# AFE.net
KiCad netlist of a schematic drawn in EAGLE
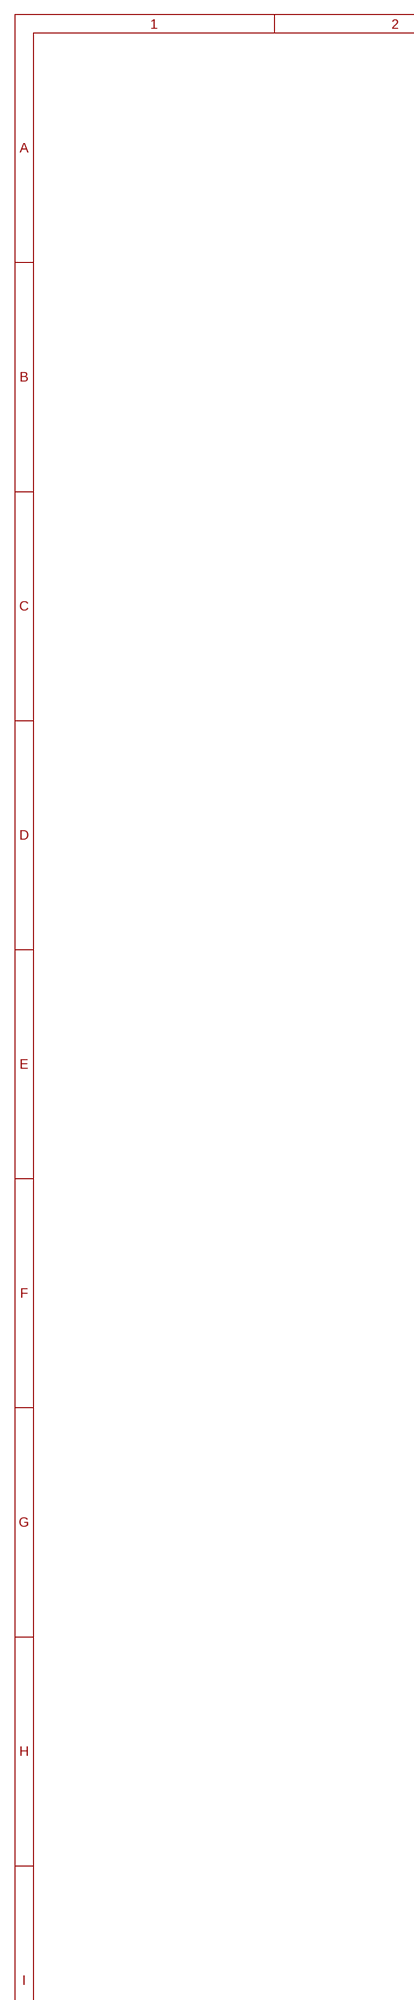
[diagram p0: schematic, sheet 1, part 1 of 2]
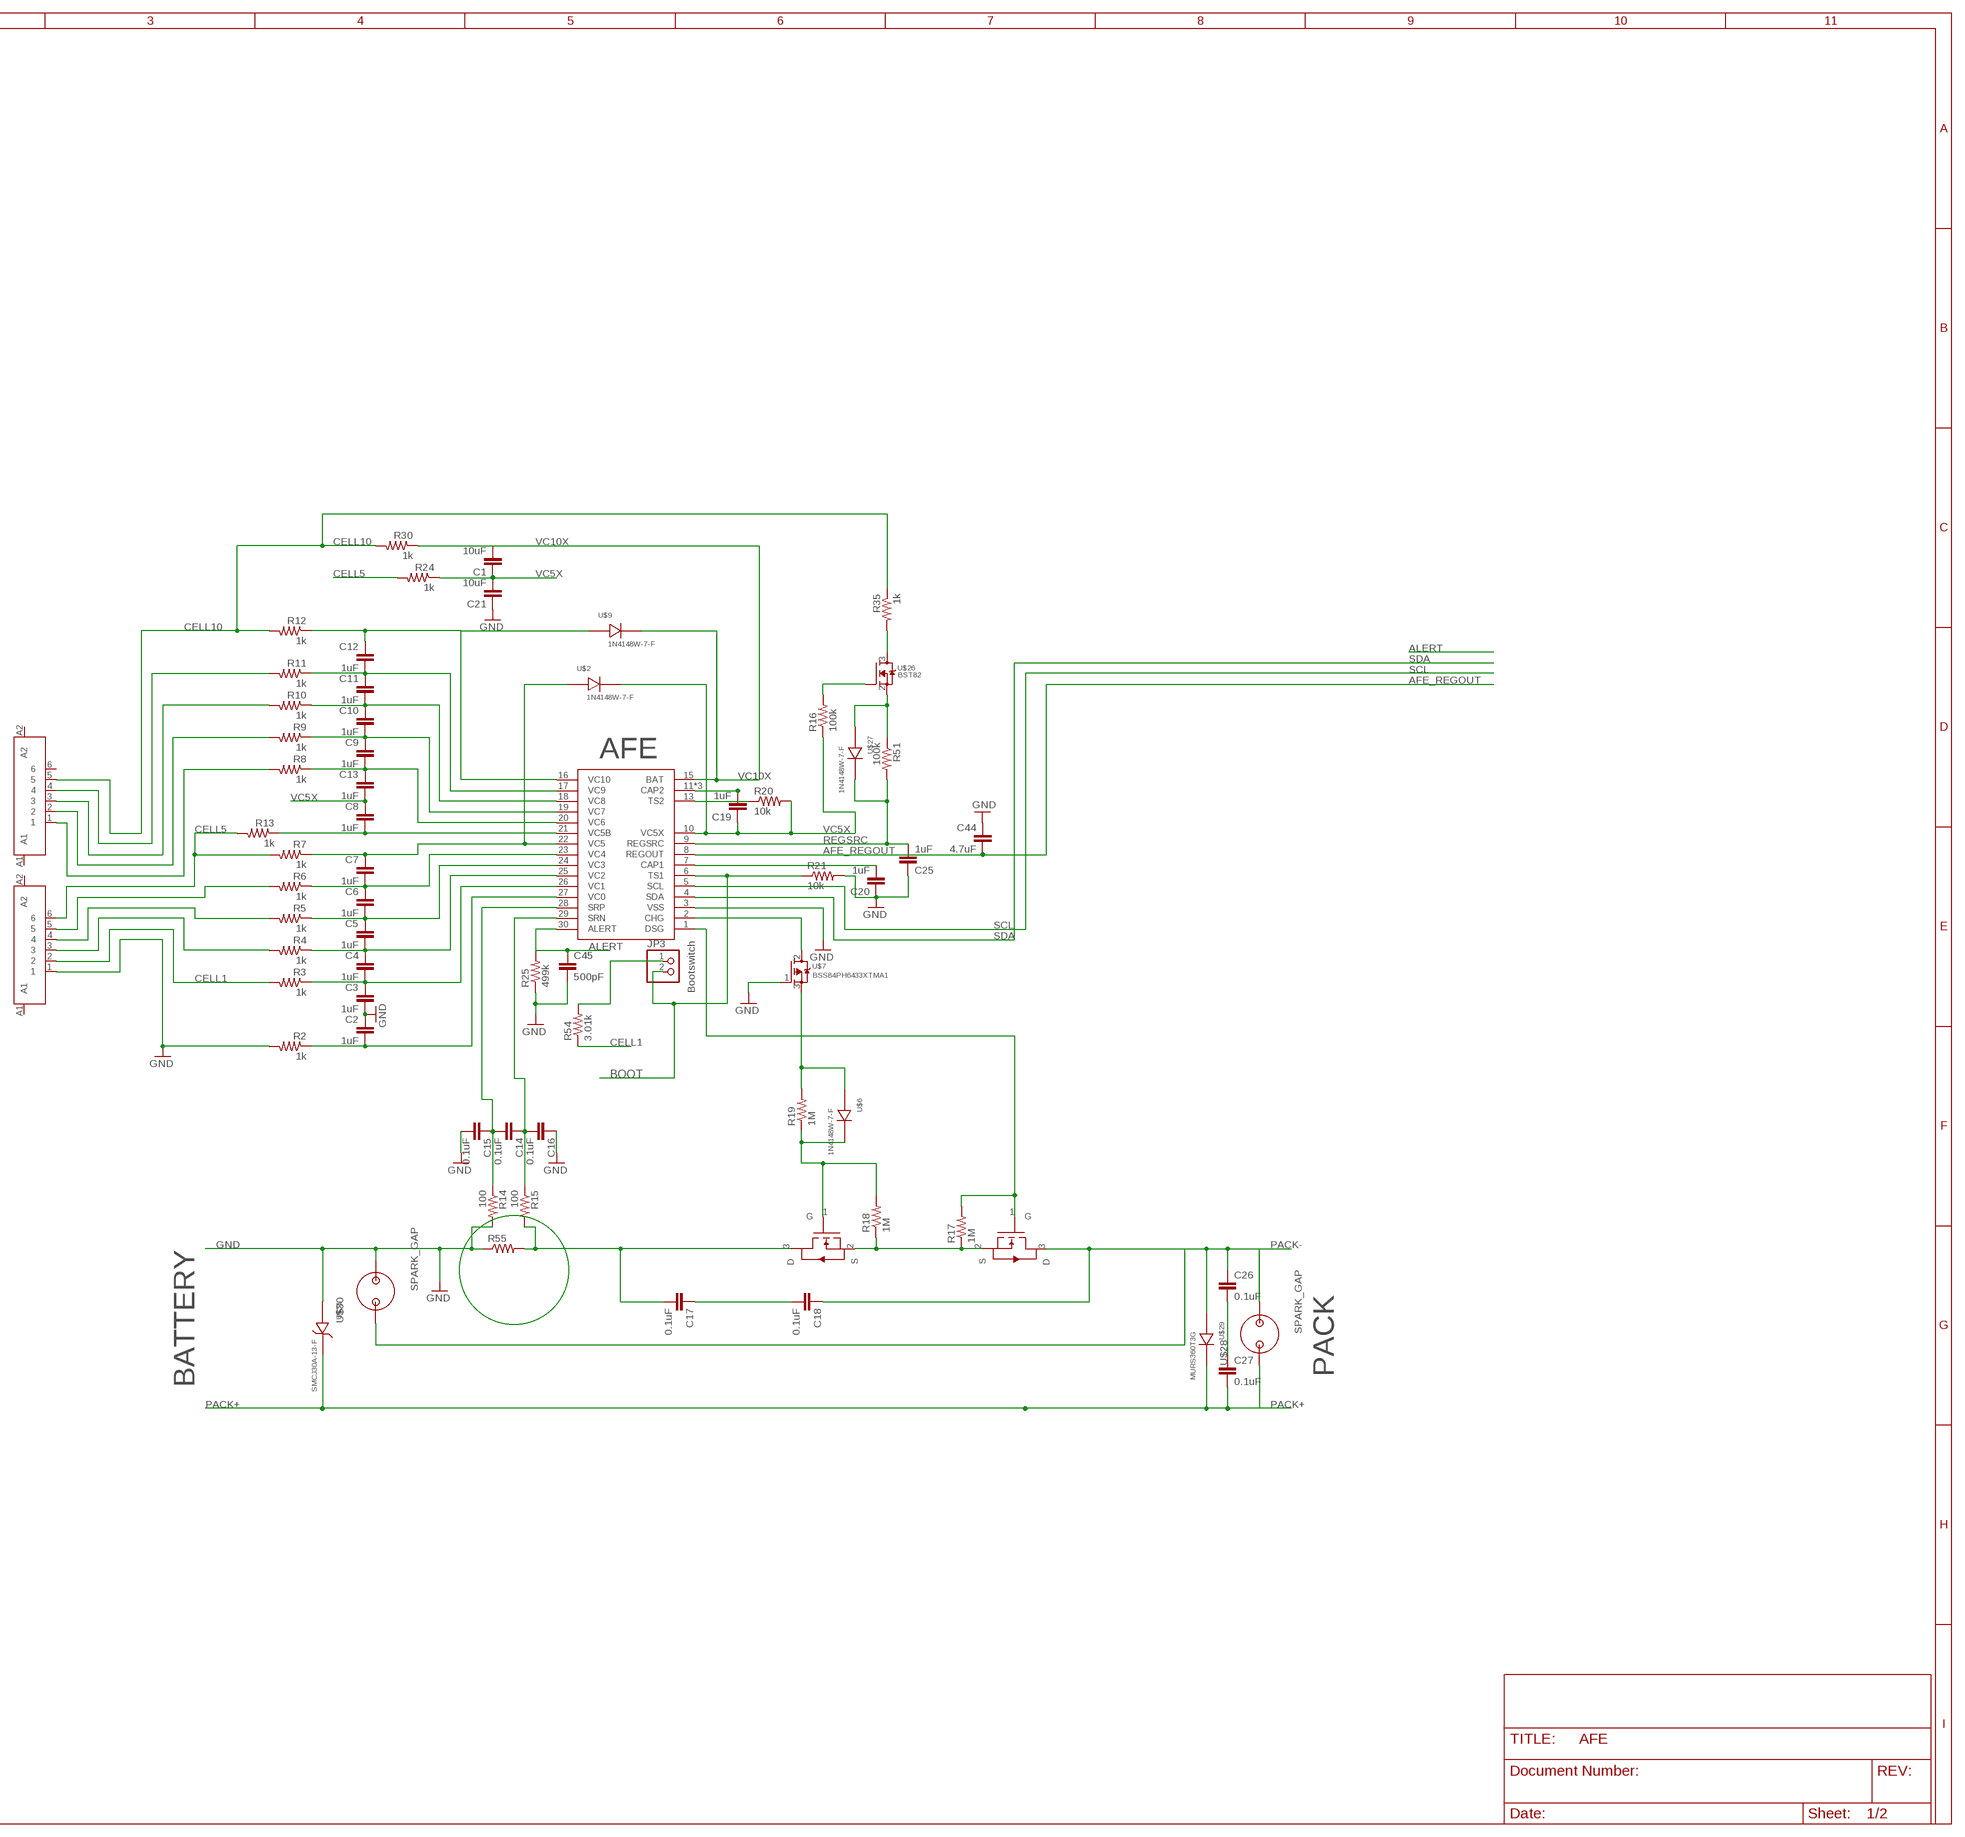
[diagram p1: schematic, sheet 1, part 2 of 2]
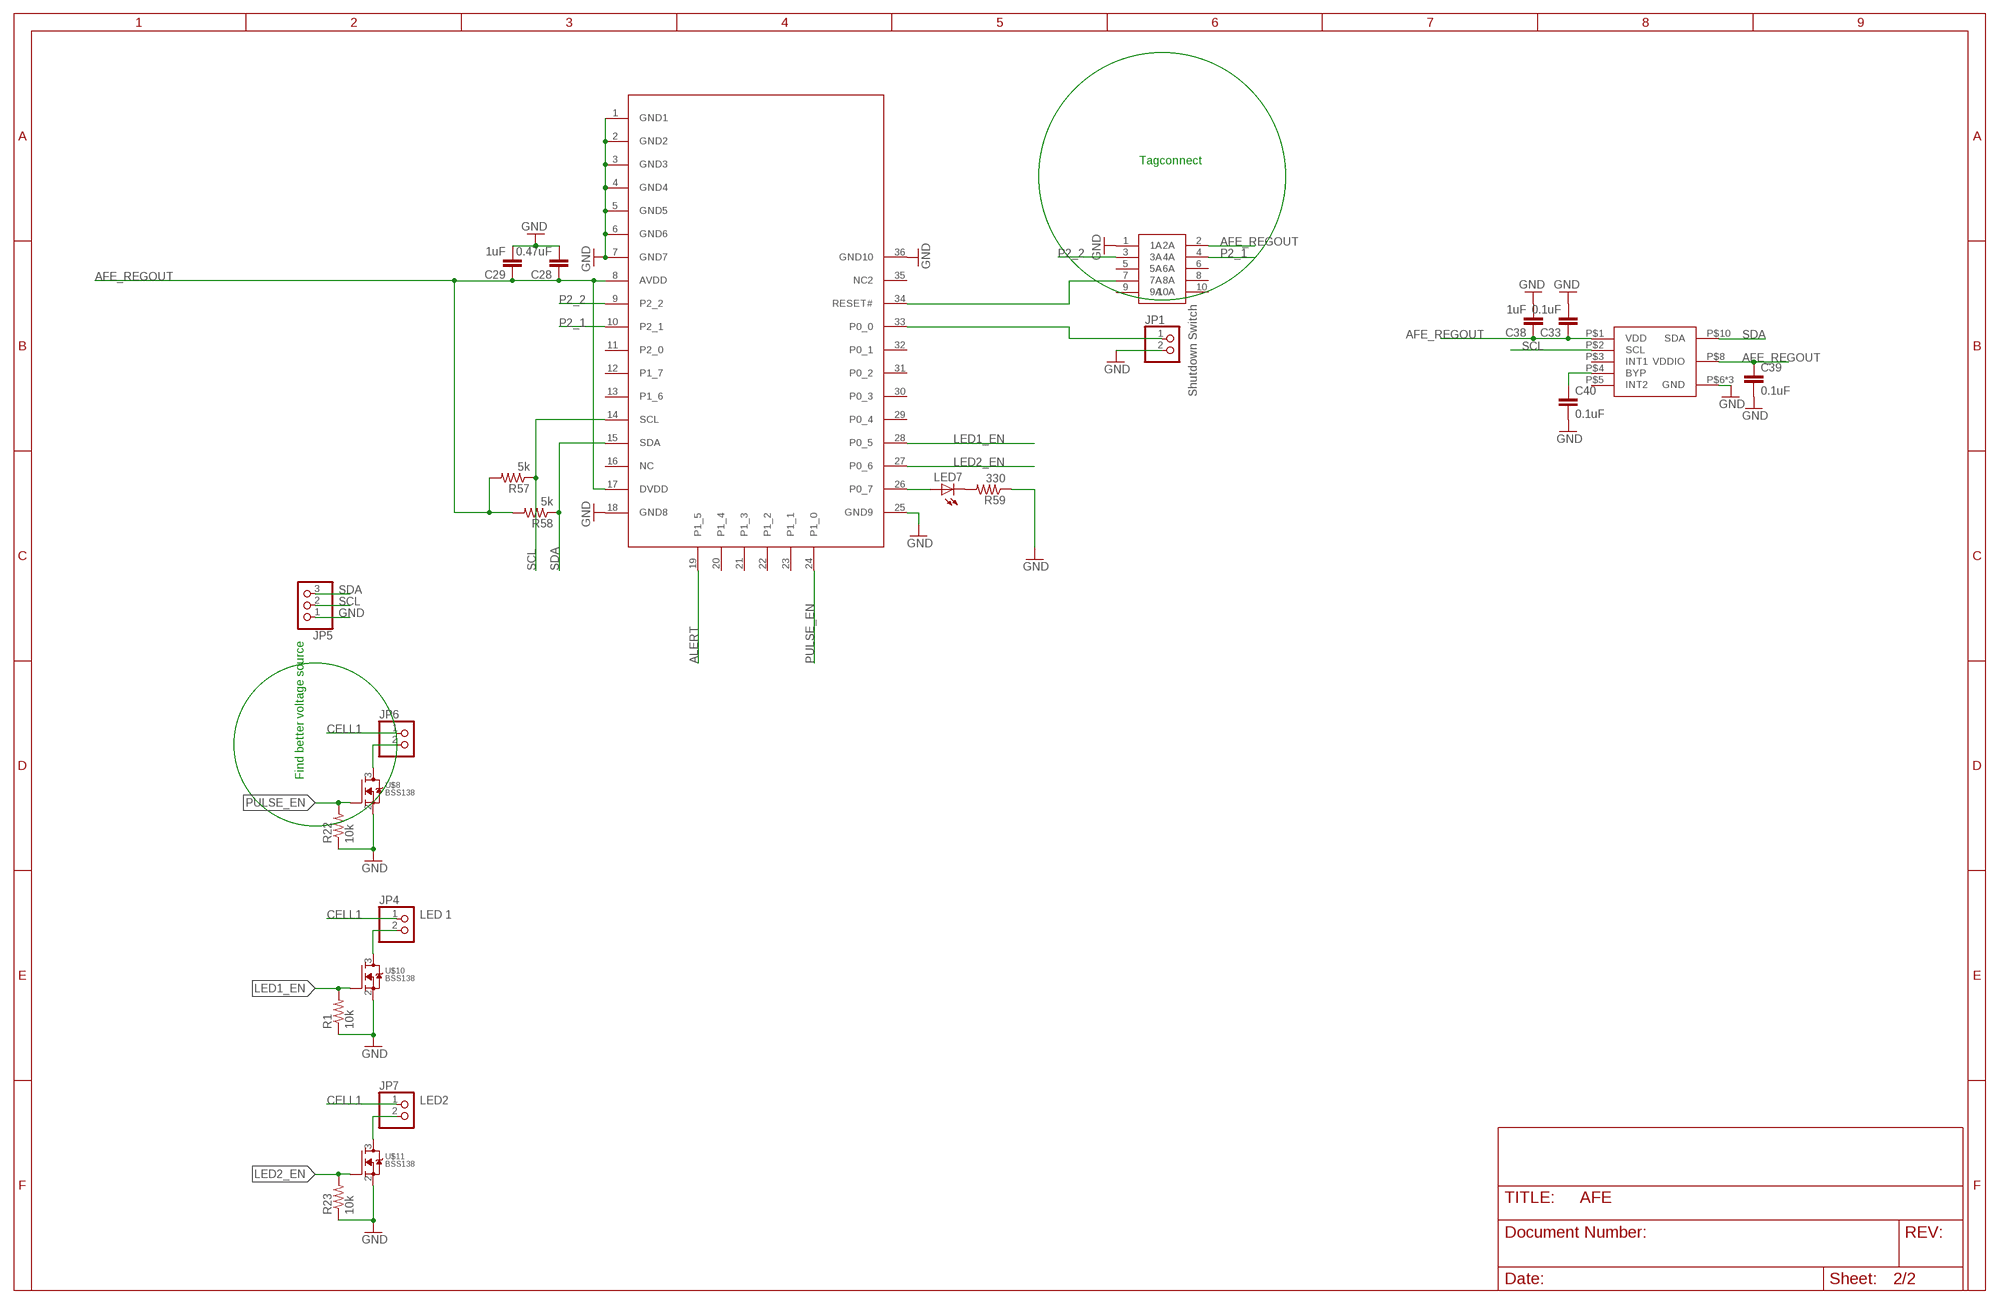
[diagram p2: schematic, sheet 2]

(export (version "E")
  (design (tool "Eeschema 10.0.6"))
  (components
    (comp (ref "C1")
      (value "10uF")
      (footprint "eagle-import:C1210")
      (libsource (lib "eagle-import") (part "C-EUC1210"))
    )
    (comp (ref "C2")
      (value "1uF")
      (footprint "eagle-import:C0805")
      (libsource (lib "eagle-import") (part "C-EUC0805"))
    )
    (comp (ref "C3")
      (value "1uF")
      (footprint "eagle-import:C0805")
      (libsource (lib "eagle-import") (part "C-EUC0805"))
    )
    (comp (ref "C4")
      (value "1uF")
      (footprint "eagle-import:C0805")
      (libsource (lib "eagle-import") (part "C-EUC0805"))
    )
    (comp (ref "C5")
      (value "1uF")
      (footprint "eagle-import:C0805")
      (libsource (lib "eagle-import") (part "C-EUC0805"))
    )
    (comp (ref "C6")
      (value "1uF")
      (footprint "eagle-import:C0805")
      (libsource (lib "eagle-import") (part "C-EUC0805"))
    )
    (comp (ref "C7")
      (value "1uF")
      (footprint "eagle-import:C0805")
      (libsource (lib "eagle-import") (part "C-EUC0805"))
    )
    (comp (ref "C8")
      (value "1uF")
      (footprint "eagle-import:C0805")
      (libsource (lib "eagle-import") (part "C-EUC0805"))
    )
    (comp (ref "C9")
      (value "1uF")
      (footprint "eagle-import:C0805")
      (libsource (lib "eagle-import") (part "C-EUC0805"))
    )
    (comp (ref "C10")
      (value "1uF")
      (footprint "eagle-import:C0805")
      (libsource (lib "eagle-import") (part "C-EUC0805"))
    )
    (comp (ref "C11")
      (value "1uF")
      (footprint "eagle-import:C0805")
      (libsource (lib "eagle-import") (part "C-EUC0805"))
    )
    (comp (ref "C12")
      (value "1uF")
      (footprint "eagle-import:C0805")
      (libsource (lib "eagle-import") (part "C-EUC0805"))
    )
    (comp (ref "C13")
      (value "1uF")
      (footprint "eagle-import:C0805")
      (libsource (lib "eagle-import") (part "C-EUC0805"))
    )
    (comp (ref "C14")
      (value "0.1uF")
      (footprint "eagle-import:C0805")
      (libsource (lib "eagle-import") (part "C-EUC0805"))
    )
    (comp (ref "C15")
      (value "0.1uF")
      (footprint "eagle-import:C0805")
      (libsource (lib "eagle-import") (part "C-EUC0805"))
    )
    (comp (ref "C16")
      (value "0.1uF")
      (footprint "eagle-import:C0805")
      (libsource (lib "eagle-import") (part "C-EUC0805"))
    )
    (comp (ref "C17")
      (value "0.1uF")
      (footprint "eagle-import:C0805")
      (libsource (lib "eagle-import") (part "C-EUC0805"))
    )
    (comp (ref "C18")
      (value "0.1uF")
      (footprint "eagle-import:C0805")
      (libsource (lib "eagle-import") (part "C-EUC0805"))
    )
    (comp (ref "C19")
      (value "1uF")
      (footprint "eagle-import:C0805")
      (libsource (lib "eagle-import") (part "C-EUC0805"))
    )
    (comp (ref "C20")
      (value "1uF")
      (footprint "eagle-import:C0805")
      (libsource (lib "eagle-import") (part "C-EUC0805"))
    )
    (comp (ref "C21")
      (value "10uF")
      (footprint "eagle-import:C1210")
      (libsource (lib "eagle-import") (part "C-EUC1210"))
    )
    (comp (ref "C25")
      (value "1uF")
      (footprint "eagle-import:C0805")
      (libsource (lib "eagle-import") (part "C-EUC0805"))
    )
    (comp (ref "C26")
      (value "0.1uF")
      (footprint "eagle-import:C0805")
      (libsource (lib "eagle-import") (part "C-EUC0805"))
    )
    (comp (ref "C27")
      (value "0.1uF")
      (footprint "eagle-import:C0805")
      (libsource (lib "eagle-import") (part "C-EUC0805"))
    )
    (comp (ref "C44")
      (value "4.7uF")
      (footprint "eagle-import:C0805")
      (libsource (lib "eagle-import") (part "C-EUC0805"))
    )
    (comp (ref "C45")
      (value "500pF")
      (footprint "eagle-import:C0603")
      (libsource (lib "eagle-import") (part "C-EUC0603"))
    )
    (comp (ref "JP3")
      (value "PINHD-1X2")
      (footprint "eagle-import:1X02")
      (libsource (lib "eagle-import") (part "PINHD-1X2"))
    )
    (comp (ref "R2")
      (value "1k")
      (footprint "eagle-import:R1206")
      (libsource (lib "eagle-import") (part "R-US_R1206"))
    )
    (comp (ref "R3")
      (value "1k")
      (footprint "eagle-import:R1206")
      (libsource (lib "eagle-import") (part "R-US_R1206"))
    )
    (comp (ref "R4")
      (value "1k")
      (footprint "eagle-import:R1206")
      (libsource (lib "eagle-import") (part "R-US_R1206"))
    )
    (comp (ref "R5")
      (value "1k")
      (footprint "eagle-import:R1206")
      (libsource (lib "eagle-import") (part "R-US_R1206"))
    )
    (comp (ref "R6")
      (value "1k")
      (footprint "eagle-import:R1206")
      (libsource (lib "eagle-import") (part "R-US_R1206"))
    )
    (comp (ref "R7")
      (value "1k")
      (footprint "eagle-import:R1206")
      (libsource (lib "eagle-import") (part "R-US_R1206"))
    )
    (comp (ref "R8")
      (value "1k")
      (footprint "eagle-import:R1206")
      (libsource (lib "eagle-import") (part "R-US_R1206"))
    )
    (comp (ref "R9")
      (value "1k")
      (footprint "eagle-import:R1206")
      (libsource (lib "eagle-import") (part "R-US_R1206"))
    )
    (comp (ref "R10")
      (value "1k")
      (footprint "eagle-import:R1206")
      (libsource (lib "eagle-import") (part "R-US_R1206"))
    )
    (comp (ref "R11")
      (value "1k")
      (footprint "eagle-import:R1206")
      (libsource (lib "eagle-import") (part "R-US_R1206"))
    )
    (comp (ref "R12")
      (value "1k")
      (footprint "eagle-import:R1206")
      (libsource (lib "eagle-import") (part "R-US_R1206"))
    )
    (comp (ref "R13")
      (value "1k")
      (footprint "eagle-import:R1206")
      (libsource (lib "eagle-import") (part "R-US_R1206"))
    )
    (comp (ref "R14")
      (value "100")
      (footprint "eagle-import:R0805")
      (libsource (lib "eagle-import") (part "R-US_R0805"))
    )
    (comp (ref "R15")
      (value "100")
      (footprint "eagle-import:R0805")
      (libsource (lib "eagle-import") (part "R-US_R0805"))
    )
    (comp (ref "R16")
      (value "100k")
      (footprint "eagle-import:R0805")
      (libsource (lib "eagle-import") (part "R-US_R0805"))
    )
    (comp (ref "R17")
      (value "1M")
      (footprint "eagle-import:R1206")
      (libsource (lib "eagle-import") (part "R-US_R1206"))
    )
    (comp (ref "R18")
      (value "1M")
      (footprint "eagle-import:R1206")
      (libsource (lib "eagle-import") (part "R-US_R1206"))
    )
    (comp (ref "R19")
      (value "1M")
      (footprint "eagle-import:R1206")
      (libsource (lib "eagle-import") (part "R-US_R1206"))
    )
    (comp (ref "R20")
      (value "10k")
      (footprint "eagle-import:R0805")
      (libsource (lib "eagle-import") (part "R-US_R0805"))
    )
    (comp (ref "R21")
      (value "10k")
      (footprint "eagle-import:R0805")
      (libsource (lib "eagle-import") (part "R-US_R0805"))
    )
    (comp (ref "R24")
      (value "1k")
      (footprint "eagle-import:R1206")
      (libsource (lib "eagle-import") (part "R-US_R1206"))
    )
    (comp (ref "R25")
      (value "499k")
      (footprint "eagle-import:R0603")
      (libsource (lib "eagle-import") (part "R-US_R0603"))
    )
    (comp (ref "R30")
      (value "1k")
      (footprint "eagle-import:R1206")
      (libsource (lib "eagle-import") (part "R-US_R1206"))
    )
    (comp (ref "R35")
      (value "1k")
      (footprint "eagle-import:R1206")
      (libsource (lib "eagle-import") (part "R-US_R1206"))
    )
    (comp (ref "R51")
      (value "100k")
      (footprint "eagle-import:R0805")
      (libsource (lib "eagle-import") (part "R-US_R0805"))
    )
    (comp (ref "R54")
      (value "3.01k")
      (footprint "eagle-import:R1206")
      (libsource (lib "eagle-import") (part "R-US_R1206"))
    )
    (comp (ref "R55")
      (value "R-US_R2512")
      (footprint "eagle-import:R2512")
      (libsource (lib "eagle-import") (part "R-US_R2512"))
    )
    (comp (ref "U$1")
      (value "BQ76930")
      (footprint "eagle-import:SOIC-30")
      (libsource (lib "eagle-import") (part "BQ76930"))
    )
    (comp (ref "U$2")
      (value "1N4148W-7-F")
      (footprint "eagle-import:SOD-123")
      (libsource (lib "eagle-import") (part "1N4148W-7-F"))
    )
    (comp (ref "U$4")
      (value "AOB290L")
      (footprint "eagle-import:TO-263")
      (libsource (lib "eagle-import") (part "AOB290L"))
    )
    (comp (ref "U$5")
      (value "AOB290L")
      (footprint "eagle-import:TO-263")
      (libsource (lib "eagle-import") (part "AOB290L"))
    )
    (comp (ref "U$6")
      (value "1N4148W-7-F")
      (footprint "eagle-import:SOD-123")
      (libsource (lib "eagle-import") (part "1N4148W-7-F"))
    )
    (comp (ref "U$7")
      (value "BSS84PH6433XTMA1")
      (footprint "eagle-import:SOT23-3")
      (libsource (lib "eagle-import") (part "BSS84PH6433XTMA1"))
    )
    (comp (ref "U$9")
      (value "1N4148W-7-F")
      (footprint "eagle-import:SOD-123")
      (libsource (lib "eagle-import") (part "1N4148W-7-F"))
    )
    (comp (ref "U$24")
      (value "JST_6PIN")
      (footprint "eagle-import:JST_6PIN")
      (libsource (lib "eagle-import") (part "JST_6PIN"))
    )
    (comp (ref "U$26")
      (value "BST82")
      (footprint "eagle-import:SOT23-3")
      (libsource (lib "eagle-import") (part "BST82"))
    )
    (comp (ref "U$27")
      (value "1N4148W-7-F")
      (footprint "eagle-import:SOD-123")
      (libsource (lib "eagle-import") (part "1N4148W-7-F"))
    )
    (comp (ref "U$28")
      (value "SPARK_GAP")
      (footprint "eagle-import:SPARK_GAP")
      (libsource (lib "eagle-import") (part "SPARK_GAP"))
    )
    (comp (ref "U$29")
      (value "MURS360T3G")
      (footprint "eagle-import:SMC(DO-214AB)")
      (libsource (lib "eagle-import") (part "MURS360T3G"))
    )
    (comp (ref "U$30")
      (value "SPARK_GAP")
      (footprint "eagle-import:SPARK_GAP")
      (libsource (lib "eagle-import") (part "SPARK_GAP"))
    )
    (comp (ref "U$31")
      (value "SMCJ30A-13-F")
      (footprint "eagle-import:SMB(DO-214AA)")
      (libsource (lib "eagle-import") (part "SMCJ30A-13-F"))
    )
    (comp (ref "U$33")
      (value "JST_6PIN")
      (footprint "eagle-import:JST_6PIN")
      (libsource (lib "eagle-import") (part "JST_6PIN"))
    )
    (comp (ref "C28")
      (value "0.47uF")
      (footprint "eagle-import:C0402")
      (libsource (lib "eagle-import") (part "C-EUC0402"))
    )
    (comp (ref "C29")
      (value "1uF")
      (footprint "eagle-import:C0402")
      (libsource (lib "eagle-import") (part "C-EUC0402"))
    )
    (comp (ref "C33")
      (value "0.1uF")
      (footprint "eagle-import:C0402")
      (libsource (lib "eagle-import") (part "C-EUC0402"))
    )
    (comp (ref "C38")
      (value "1uF")
      (footprint "eagle-import:C0402")
      (libsource (lib "eagle-import") (part "C-EUC0402"))
    )
    (comp (ref "C39")
      (value "0.1uF")
      (footprint "eagle-import:C0402")
      (libsource (lib "eagle-import") (part "C-EUC0402"))
    )
    (comp (ref "C40")
      (value "0.1uF")
      (footprint "eagle-import:C0402")
      (libsource (lib "eagle-import") (part "C-EUC0402"))
    )
    (comp (ref "JP1")
      (value "PINHD-1X2")
      (footprint "eagle-import:1X02")
      (libsource (lib "eagle-import") (part "PINHD-1X2"))
    )
    (comp (ref "JP4")
      (value "PINHD-1X2")
      (footprint "eagle-import:1X02")
      (libsource (lib "eagle-import") (part "PINHD-1X2"))
    )
    (comp (ref "JP5")
      (value "PINHD-1X3")
      (footprint "eagle-import:1X03")
      (libsource (lib "eagle-import") (part "PINHD-1X3"))
    )
    (comp (ref "JP6")
      (value "PINHD-1X2")
      (footprint "eagle-import:1X02")
      (libsource (lib "eagle-import") (part "PINHD-1X2"))
    )
    (comp (ref "JP7")
      (value "PINHD-1X2")
      (footprint "eagle-import:1X02")
      (libsource (lib "eagle-import") (part "PINHD-1X2"))
    )
    (comp (ref "LED7")
      (value "LEDCHIP-LED0603")
      (footprint "eagle-import:CHIP-LED0603")
      (libsource (lib "eagle-import") (part "LEDCHIP-LED0603"))
    )
    (comp (ref "R1")
      (value "10k")
      (footprint "eagle-import:R0402")
      (libsource (lib "eagle-import") (part "R-US_R0402"))
    )
    (comp (ref "R22")
      (value "10k")
      (footprint "eagle-import:R0402")
      (libsource (lib "eagle-import") (part "R-US_R0402"))
    )
    (comp (ref "R23")
      (value "10k")
      (footprint "eagle-import:R0402")
      (libsource (lib "eagle-import") (part "R-US_R0402"))
    )
    (comp (ref "R57")
      (value "5k")
      (footprint "eagle-import:R0402")
      (libsource (lib "eagle-import") (part "R-US_R0402"))
    )
    (comp (ref "R58")
      (value "5k")
      (footprint "eagle-import:R0402")
      (libsource (lib "eagle-import") (part "R-US_R0402"))
    )
    (comp (ref "R59")
      (value "330")
      (footprint "eagle-import:R0402")
      (libsource (lib "eagle-import") (part "R-US_R0402"))
    )
    (comp (ref "U$8")
      (value "BSS138")
      (footprint "eagle-import:SOT23-3")
      (libsource (lib "eagle-import") (part "BSS138"))
    )
    (comp (ref "U$10")
      (value "BSS138")
      (footprint "eagle-import:SOT23-3")
      (libsource (lib "eagle-import") (part "BSS138"))
    )
    (comp (ref "U$11")
      (value "BSS138")
      (footprint "eagle-import:SOT23-3")
      (libsource (lib "eagle-import") (part "BSS138"))
    )
    (comp (ref "U$20")
      (value "BLE113")
      (footprint "eagle-import:BLUEGIGA")
      (libsource (lib "eagle-import") (part "BLE113"))
    )
    (comp (ref "U$22")
      (value "RIBBON_10POS_MALE")
      (footprint "eagle-import:RIBBON_10POS_MALE")
      (libsource (lib "eagle-import") (part "RIBBON_10POS_MALE"))
    )
    (comp (ref "U$32")
      (value "MMA8653FC")
      (footprint "eagle-import:10-DFN2X2")
      (libsource (lib "eagle-import") (part "MMA8653FC"))
    )
  )
  (nets
    (net (code "1") (name "AFE_REGOUT") (class "Default")
      (node (ref "C28") (pin "1") (pinfunction "1_1") (pintype "passive"))
      (node (ref "C29") (pin "1") (pinfunction "1_1") (pintype "passive"))
      (node (ref "C33") (pin "1") (pinfunction "1_1") (pintype "passive"))
      (node (ref "C38") (pin "1") (pinfunction "1_1") (pintype "passive"))
      (node (ref "C39") (pin "1") (pinfunction "1_1") (pintype "passive"))
      (node (ref "C44") (pin "2") (pinfunction "2_2") (pintype "passive"))
      (node (ref "R57") (pin "2") (pinfunction "2_2") (pintype "passive"))
      (node (ref "R58") (pin "2") (pinfunction "2_2") (pintype "passive"))
      (node (ref "U$1") (pin "8") (pinfunction "REGOUT_8") (pintype "bidirectional"))
      (node (ref "U$20") (pin "17") (pinfunction "DVDD_17") (pintype "bidirectional"))
      (node (ref "U$20") (pin "8") (pinfunction "AVDD_8") (pintype "bidirectional"))
      (node (ref "U$22") (pin "2") (pinfunction "2A_2") (pintype "bidirectional"))
      (node (ref "U$32") (pin "P$1") (pinfunction "VDD_P$1") (pintype "bidirectional"))
      (node (ref "U$32") (pin "P$8") (pinfunction "VDDIO_P$8") (pintype "bidirectional"))
    )
    (net (code "2") (name "ALERT") (class "Default")
      (node (ref "C45") (pin "1") (pinfunction "1_1") (pintype "passive"))
      (node (ref "R25") (pin "2") (pinfunction "2_2") (pintype "passive"))
      (node (ref "U$1") (pin "30") (pinfunction "ALERT_30") (pintype "bidirectional"))
      (node (ref "U$20") (pin "19") (pinfunction "P1_5_19") (pintype "bidirectional"))
    )
    (net (code "3") (name "BOOT") (class "Default")
      (node (ref "JP3") (pin "2") (pinfunction "2_2") (pintype "passive"))
      (node (ref "R21") (pin "1") (pinfunction "1_1") (pintype "passive"))
      (node (ref "U$1") (pin "6") (pinfunction "TS1_6") (pintype "bidirectional"))
    )
    (net (code "4") (name "CELL1") (class "Default")
      (node (ref "JP4") (pin "1") (pinfunction "1_1") (pintype "passive"))
      (node (ref "JP6") (pin "1") (pinfunction "1_1") (pintype "passive"))
      (node (ref "JP7") (pin "1") (pinfunction "1_1") (pintype "passive"))
      (node (ref "R3") (pin "2") (pinfunction "2_2") (pintype "passive"))
      (node (ref "R54") (pin "1") (pinfunction "1_1") (pintype "passive"))
      (node (ref "U$33") (pin "2") (pinfunction "2_2") (pintype "bidirectional"))
    )
    (net (code "5") (name "CELL5") (class "Default")
      (node (ref "R13") (pin "2") (pinfunction "2_2") (pintype "passive"))
      (node (ref "R24") (pin "2") (pinfunction "2_2") (pintype "passive"))
      (node (ref "R7") (pin "2") (pinfunction "2_2") (pintype "passive"))
      (node (ref "U$33") (pin "6") (pinfunction "6_6") (pintype "bidirectional"))
    )
    (net (code "6") (name "CELL10") (class "Default")
      (node (ref "R12") (pin "2") (pinfunction "2_2") (pintype "passive"))
      (node (ref "R30") (pin "2") (pinfunction "2_2") (pintype "passive"))
      (node (ref "R35") (pin "1") (pinfunction "1_1") (pintype "passive"))
      (node (ref "U$24") (pin "5") (pinfunction "5_5") (pintype "bidirectional"))
    )
    (net (code "7") (name "GND") (class "Default")
      (node (ref "C15") (pin "2") (pinfunction "2_2") (pintype "passive"))
      (node (ref "C16") (pin "1") (pinfunction "1_1") (pintype "passive"))
      (node (ref "C2") (pin "1") (pinfunction "1_1") (pintype "passive"))
      (node (ref "C20") (pin "1") (pinfunction "1_1") (pintype "passive"))
      (node (ref "C21") (pin "1") (pinfunction "1_1") (pintype "passive"))
      (node (ref "C25") (pin "1") (pinfunction "1_1") (pintype "passive"))
      (node (ref "C28") (pin "2") (pinfunction "2_2") (pintype "passive"))
      (node (ref "C29") (pin "2") (pinfunction "2_2") (pintype "passive"))
      (node (ref "C3") (pin "2") (pinfunction "2_2") (pintype "passive"))
      (node (ref "C33") (pin "2") (pinfunction "2_2") (pintype "passive"))
      (node (ref "C38") (pin "2") (pinfunction "2_2") (pintype "passive"))
      (node (ref "C39") (pin "2") (pinfunction "2_2") (pintype "passive"))
      (node (ref "C40") (pin "2") (pinfunction "2_2") (pintype "passive"))
      (node (ref "C44") (pin "1") (pinfunction "1_1") (pintype "passive"))
      (node (ref "C45") (pin "2") (pinfunction "2_2") (pintype "passive"))
      (node (ref "JP1") (pin "2") (pinfunction "2_2") (pintype "passive"))
      (node (ref "JP5") (pin "1") (pinfunction "1_1") (pintype "passive"))
      (node (ref "R1") (pin "1") (pinfunction "1_1") (pintype "passive"))
      (node (ref "R14") (pin "2") (pinfunction "2_2") (pintype "passive"))
      (node (ref "R2") (pin "2") (pinfunction "2_2") (pintype "passive"))
      (node (ref "R21") (pin "2") (pinfunction "2_2") (pintype "passive"))
      (node (ref "R22") (pin "1") (pinfunction "1_1") (pintype "passive"))
      (node (ref "R23") (pin "1") (pinfunction "1_1") (pintype "passive"))
      (node (ref "R25") (pin "1") (pinfunction "1_1") (pintype "passive"))
      (node (ref "R55") (pin "1") (pinfunction "1_1") (pintype "passive"))
      (node (ref "R59") (pin "1") (pinfunction "1_1") (pintype "passive"))
      (node (ref "U$1") (pin "3") (pinfunction "VSS_3") (pintype "bidirectional"))
      (node (ref "U$10") (pin "2") (pinfunction "S_2") (pintype "bidirectional"))
      (node (ref "U$11") (pin "2") (pinfunction "S_2") (pintype "bidirectional"))
      (node (ref "U$20") (pin "1") (pinfunction "GND1_1") (pintype "bidirectional"))
      (node (ref "U$20") (pin "18") (pinfunction "GND8_18") (pintype "bidirectional"))
      (node (ref "U$20") (pin "2") (pinfunction "GND2_2") (pintype "bidirectional"))
      (node (ref "U$20") (pin "25") (pinfunction "GND9_25") (pintype "bidirectional"))
      (node (ref "U$20") (pin "3") (pinfunction "GND3_3") (pintype "bidirectional"))
      (node (ref "U$20") (pin "36") (pinfunction "GND10_36") (pintype "bidirectional"))
      (node (ref "U$20") (pin "4") (pinfunction "GND4_4") (pintype "bidirectional"))
      (node (ref "U$20") (pin "5") (pinfunction "GND5_5") (pintype "bidirectional"))
      (node (ref "U$20") (pin "6") (pinfunction "GND6_6") (pintype "bidirectional"))
      (node (ref "U$20") (pin "7") (pinfunction "GND7_7") (pintype "bidirectional"))
      (node (ref "U$22") (pin "1") (pinfunction "1A_1") (pintype "bidirectional"))
      (node (ref "U$30") (pin "P$2") (pinfunction "P$2_P$2") (pintype "bidirectional"))
      (node (ref "U$31") (pin "P$1") (pinfunction "1_P$1") (pintype "bidirectional"))
      (node (ref "U$32") (pin "P$6") (pinfunction "GND_P$6") (pintype "bidirectional"))
      (node (ref "U$32") (pin "P$7") (pinfunction "GND_P$7") (pintype "bidirectional"))
      (node (ref "U$32") (pin "P$9") (pinfunction "GND_P$9") (pintype "bidirectional"))
      (node (ref "U$33") (pin "1") (pinfunction "1_1") (pintype "bidirectional"))
      (node (ref "U$7") (pin "1") (pinfunction "G_1") (pintype "bidirectional"))
      (node (ref "U$8") (pin "2") (pinfunction "S_2") (pintype "bidirectional"))
    )
    (net (code "8") (name "LED1_EN") (class "Default")
      (node (ref "R1") (pin "2") (pinfunction "2_2") (pintype "passive"))
      (node (ref "U$10") (pin "1") (pinfunction "G_1") (pintype "bidirectional"))
      (node (ref "U$20") (pin "28") (pinfunction "P0_5_28") (pintype "bidirectional"))
    )
    (net (code "9") (name "LED2_EN") (class "Default")
      (node (ref "R23") (pin "2") (pinfunction "2_2") (pintype "passive"))
      (node (ref "U$11") (pin "1") (pinfunction "G_1") (pintype "bidirectional"))
      (node (ref "U$20") (pin "27") (pinfunction "P0_6_27") (pintype "bidirectional"))
    )
    (net (code "10") (name "Net-(C17-Pad1)") (class "Default")
      (node (ref "C17") (pin "1") (pinfunction "1_1") (pintype "passive"))
      (node (ref "C18") (pin "2") (pinfunction "2_2") (pintype "passive"))
    )
    (net (code "11") (name "Net-(C19-Pad2)") (class "Default")
      (node (ref "C19") (pin "2") (pinfunction "2_2") (pintype "passive"))
      (node (ref "U$1") (pin "11") (pinfunction "CAP2_11") (pintype "bidirectional"))
      (node (ref "U$1") (pin "12") (pinfunction "CAP2_12") (pintype "bidirectional"))
      (node (ref "U$1") (pin "14") (pinfunction "CAP2_14") (pintype "bidirectional"))
    )
    (net (code "12") (name "Net-(C26-Pad2)") (class "Default")
      (node (ref "C26") (pin "2") (pinfunction "2_2") (pintype "passive"))
      (node (ref "C27") (pin "1") (pinfunction "1_1") (pintype "passive"))
    )
    (net (code "13") (name "Net-(JP3-Pad1)") (class "Default")
      (node (ref "JP3") (pin "1") (pinfunction "1_1") (pintype "passive"))
      (node (ref "R54") (pin "2") (pinfunction "2_2") (pintype "passive"))
    )
    (net (code "14") (name "Net-(LED7-PadC)") (class "Default")
      (node (ref "LED7") (pin "C") (pinfunction "C_C") (pintype "passive"))
      (node (ref "R59") (pin "2") (pinfunction "2_2") (pintype "passive"))
    )
    (net (code "15") (name "Net-(R4-Pad2)") (class "Default")
      (node (ref "R4") (pin "2") (pinfunction "2_2") (pintype "passive"))
      (node (ref "U$33") (pin "3") (pinfunction "3_3") (pintype "bidirectional"))
    )
    (net (code "16") (name "Net-(R5-Pad2)") (class "Default")
      (node (ref "R5") (pin "2") (pinfunction "2_2") (pintype "passive"))
      (node (ref "U$33") (pin "4") (pinfunction "4_4") (pintype "bidirectional"))
    )
    (net (code "17") (name "Net-(R6-Pad2)") (class "Default")
      (node (ref "R6") (pin "2") (pinfunction "2_2") (pintype "passive"))
      (node (ref "U$33") (pin "5") (pinfunction "5_5") (pintype "bidirectional"))
    )
    (net (code "18") (name "Net-(R8-Pad2)") (class "Default")
      (node (ref "R8") (pin "2") (pinfunction "2_2") (pintype "passive"))
      (node (ref "U$24") (pin "1") (pinfunction "1_1") (pintype "bidirectional"))
    )
    (net (code "19") (name "Net-(R9-Pad2)") (class "Default")
      (node (ref "R9") (pin "2") (pinfunction "2_2") (pintype "passive"))
      (node (ref "U$24") (pin "2") (pinfunction "2_2") (pintype "bidirectional"))
    )
    (net (code "20") (name "Net-(R10-Pad2)") (class "Default")
      (node (ref "R10") (pin "2") (pinfunction "2_2") (pintype "passive"))
      (node (ref "U$24") (pin "3") (pinfunction "3_3") (pintype "bidirectional"))
    )
    (net (code "21") (name "Net-(R11-Pad2)") (class "Default")
      (node (ref "R11") (pin "2") (pinfunction "2_2") (pintype "passive"))
      (node (ref "U$24") (pin "4") (pinfunction "4_4") (pintype "bidirectional"))
    )
    (net (code "22") (name "Net-(U$1-CAP1)") (class "Default")
      (node (ref "C20") (pin "2") (pinfunction "2_2") (pintype "passive"))
      (node (ref "U$1") (pin "7") (pinfunction "CAP1_7") (pintype "bidirectional"))
    )
    (net (code "23") (name "Net-(U$1-CHG)") (class "Default")
      (node (ref "U$1") (pin "2") (pinfunction "CHG_2") (pintype "bidirectional"))
      (node (ref "U$7") (pin "2") (pinfunction "S_2") (pintype "bidirectional"))
    )
    (net (code "24") (name "Net-(U$1-DSG)") (class "Default")
      (node (ref "R17") (pin "2") (pinfunction "2_2") (pintype "passive"))
      (node (ref "U$1") (pin "1") (pinfunction "DSG_1") (pintype "bidirectional"))
      (node (ref "U$4") (pin "1") (pinfunction "G_1") (pintype "bidirectional"))
    )
    (net (code "25") (name "Net-(U$1-SRN)") (class "Default")
      (node (ref "C14") (pin "1") (pinfunction "1_1") (pintype "passive"))
      (node (ref "C16") (pin "2") (pinfunction "2_2") (pintype "passive"))
      (node (ref "R15") (pin "1") (pinfunction "1_1") (pintype "passive"))
      (node (ref "U$1") (pin "29") (pinfunction "SRN_29") (pintype "bidirectional"))
    )
    (net (code "26") (name "Net-(U$1-SRP)") (class "Default")
      (node (ref "C14") (pin "2") (pinfunction "2_2") (pintype "passive"))
      (node (ref "C15") (pin "1") (pinfunction "1_1") (pintype "passive"))
      (node (ref "R14") (pin "1") (pinfunction "1_1") (pintype "passive"))
      (node (ref "U$1") (pin "28") (pinfunction "SRP_28") (pintype "bidirectional"))
    )
    (net (code "27") (name "Net-(U$1-TS2)") (class "Default")
      (node (ref "R20") (pin "1") (pinfunction "1_1") (pintype "passive"))
      (node (ref "U$1") (pin "13") (pinfunction "TS2_13") (pintype "bidirectional"))
    )
    (net (code "28") (name "Net-(U$1-VC0)") (class "Default")
      (node (ref "C2") (pin "2") (pinfunction "2_2") (pintype "passive"))
      (node (ref "R2") (pin "1") (pinfunction "1_1") (pintype "passive"))
      (node (ref "U$1") (pin "27") (pinfunction "VC0_27") (pintype "bidirectional"))
    )
    (net (code "29") (name "Net-(U$1-VC1)") (class "Default")
      (node (ref "C3") (pin "1") (pinfunction "1_1") (pintype "passive"))
      (node (ref "C4") (pin "2") (pinfunction "2_2") (pintype "passive"))
      (node (ref "R3") (pin "1") (pinfunction "1_1") (pintype "passive"))
      (node (ref "U$1") (pin "26") (pinfunction "VC1_26") (pintype "bidirectional"))
    )
    (net (code "30") (name "Net-(U$1-VC2)") (class "Default")
      (node (ref "C4") (pin "1") (pinfunction "1_1") (pintype "passive"))
      (node (ref "C5") (pin "2") (pinfunction "2_2") (pintype "passive"))
      (node (ref "R4") (pin "1") (pinfunction "1_1") (pintype "passive"))
      (node (ref "U$1") (pin "25") (pinfunction "VC2_25") (pintype "bidirectional"))
    )
    (net (code "31") (name "Net-(U$1-VC3)") (class "Default")
      (node (ref "C5") (pin "1") (pinfunction "1_1") (pintype "passive"))
      (node (ref "C6") (pin "2") (pinfunction "2_2") (pintype "passive"))
      (node (ref "R5") (pin "1") (pinfunction "1_1") (pintype "passive"))
      (node (ref "U$1") (pin "24") (pinfunction "VC3_24") (pintype "bidirectional"))
    )
    (net (code "32") (name "Net-(U$1-VC4)") (class "Default")
      (node (ref "C6") (pin "1") (pinfunction "1_1") (pintype "passive"))
      (node (ref "C7") (pin "2") (pinfunction "2_2") (pintype "passive"))
      (node (ref "R6") (pin "1") (pinfunction "1_1") (pintype "passive"))
      (node (ref "U$1") (pin "23") (pinfunction "VC4_23") (pintype "bidirectional"))
    )
    (net (code "33") (name "Net-(U$1-VC5)") (class "Default")
      (node (ref "C7") (pin "1") (pinfunction "1_1") (pintype "passive"))
      (node (ref "R7") (pin "1") (pinfunction "1_1") (pintype "passive"))
      (node (ref "U$1") (pin "22") (pinfunction "VC5_22") (pintype "bidirectional"))
      (node (ref "U$2") (pin "P$1") (pinfunction "P$1_P$1") (pintype "bidirectional"))
    )
    (net (code "34") (name "Net-(U$1-VC5B)") (class "Default")
      (node (ref "C8") (pin "2") (pinfunction "2_2") (pintype "passive"))
      (node (ref "R13") (pin "1") (pinfunction "1_1") (pintype "passive"))
      (node (ref "U$1") (pin "21") (pinfunction "VC5B_21") (pintype "bidirectional"))
    )
    (net (code "35") (name "Net-(U$1-VC6)") (class "Default")
      (node (ref "C13") (pin "1") (pinfunction "1_1") (pintype "passive"))
      (node (ref "C9") (pin "2") (pinfunction "2_2") (pintype "passive"))
      (node (ref "R8") (pin "1") (pinfunction "1_1") (pintype "passive"))
      (node (ref "U$1") (pin "20") (pinfunction "VC6_20") (pintype "bidirectional"))
    )
    (net (code "36") (name "Net-(U$1-VC7)") (class "Default")
      (node (ref "C10") (pin "2") (pinfunction "2_2") (pintype "passive"))
      (node (ref "C9") (pin "1") (pinfunction "1_1") (pintype "passive"))
      (node (ref "R9") (pin "1") (pinfunction "1_1") (pintype "passive"))
      (node (ref "U$1") (pin "19") (pinfunction "VC7_19") (pintype "bidirectional"))
    )
    (net (code "37") (name "Net-(U$1-VC8)") (class "Default")
      (node (ref "C10") (pin "1") (pinfunction "1_1") (pintype "passive"))
      (node (ref "C11") (pin "2") (pinfunction "2_2") (pintype "passive"))
      (node (ref "R10") (pin "1") (pinfunction "1_1") (pintype "passive"))
      (node (ref "U$1") (pin "18") (pinfunction "VC8_18") (pintype "bidirectional"))
    )
    (net (code "38") (name "Net-(U$1-VC9)") (class "Default")
      (node (ref "C11") (pin "1") (pinfunction "1_1") (pintype "passive"))
      (node (ref "C12") (pin "2") (pinfunction "2_2") (pintype "passive"))
      (node (ref "R11") (pin "1") (pinfunction "1_1") (pintype "passive"))
      (node (ref "U$1") (pin "17") (pinfunction "VC9_17") (pintype "bidirectional"))
    )
    (net (code "39") (name "Net-(U$1-VC10)") (class "Default")
      (node (ref "C12") (pin "1") (pinfunction "1_1") (pintype "passive"))
      (node (ref "R12") (pin "1") (pinfunction "1_1") (pintype "passive"))
      (node (ref "U$1") (pin "16") (pinfunction "VC10_16") (pintype "bidirectional"))
      (node (ref "U$9") (pin "P$1") (pinfunction "P$1_P$1") (pintype "bidirectional"))
    )
    (net (code "40") (name "Net-(U$4-S)") (class "Default")
      (node (ref "R17") (pin "1") (pinfunction "1_1") (pintype "passive"))
      (node (ref "R18") (pin "1") (pinfunction "1_1") (pintype "passive"))
      (node (ref "U$4") (pin "2") (pinfunction "S_2") (pintype "bidirectional"))
      (node (ref "U$5") (pin "2") (pinfunction "S_2") (pintype "bidirectional"))
    )
    (net (code "41") (name "Net-(U$5-D)") (class "Default")
      (node (ref "C17") (pin "2") (pinfunction "2_2") (pintype "passive"))
      (node (ref "R15") (pin "2") (pinfunction "2_2") (pintype "passive"))
      (node (ref "R55") (pin "2") (pinfunction "2_2") (pintype "passive"))
      (node (ref "U$5") (pin "3") (pinfunction "D_3") (pintype "bidirectional"))
    )
    (net (code "42") (name "Net-(U$5-G)") (class "Default")
      (node (ref "R18") (pin "2") (pinfunction "2_2") (pintype "passive"))
      (node (ref "R19") (pin "1") (pinfunction "1_1") (pintype "passive"))
      (node (ref "U$5") (pin "1") (pinfunction "G_1") (pintype "bidirectional"))
      (node (ref "U$6") (pin "P$2") (pinfunction "P$2_P$2") (pintype "bidirectional"))
    )
    (net (code "43") (name "Net-(U$7-D)") (class "Default")
      (node (ref "R19") (pin "2") (pinfunction "2_2") (pintype "passive"))
      (node (ref "U$6") (pin "P$1") (pinfunction "P$1_P$1") (pintype "bidirectional"))
      (node (ref "U$7") (pin "3") (pinfunction "D_3") (pintype "bidirectional"))
    )
    (net (code "44") (name "Net-(U$8-D)") (class "Default")
      (node (ref "JP6") (pin "2") (pinfunction "2_2") (pintype "passive"))
      (node (ref "U$8") (pin "3") (pinfunction "D_3") (pintype "bidirectional"))
    )
    (net (code "45") (name "Net-(U$10-D)") (class "Default")
      (node (ref "JP4") (pin "2") (pinfunction "2_2") (pintype "passive"))
      (node (ref "U$10") (pin "3") (pinfunction "D_3") (pintype "bidirectional"))
    )
    (net (code "46") (name "Net-(U$11-D)") (class "Default")
      (node (ref "JP7") (pin "2") (pinfunction "2_2") (pintype "passive"))
      (node (ref "U$11") (pin "3") (pinfunction "D_3") (pintype "bidirectional"))
    )
    (net (code "47") (name "Net-(U$20-P0_0)") (class "Default")
      (node (ref "JP1") (pin "1") (pinfunction "1_1") (pintype "passive"))
      (node (ref "U$20") (pin "33") (pinfunction "P0_0_33") (pintype "bidirectional"))
    )
    (net (code "48") (name "Net-(U$20-P0_7)") (class "Default")
      (node (ref "LED7") (pin "A") (pinfunction "A_A") (pintype "passive"))
      (node (ref "U$20") (pin "26") (pinfunction "P0_7_26") (pintype "bidirectional"))
    )
    (net (code "49") (name "Net-(U$20-RESET#)") (class "Default")
      (node (ref "U$20") (pin "34") (pinfunction "RESET#_34") (pintype "bidirectional"))
      (node (ref "U$22") (pin "7") (pinfunction "7A_7") (pintype "bidirectional"))
    )
    (net (code "50") (name "Net-(U$26-D)") (class "Default")
      (node (ref "R35") (pin "2") (pinfunction "2_2") (pintype "passive"))
      (node (ref "U$26") (pin "3") (pinfunction "D_3") (pintype "bidirectional"))
    )
    (net (code "51") (name "Net-(U$26-G)") (class "Default")
      (node (ref "R16") (pin "2") (pinfunction "2_2") (pintype "passive"))
      (node (ref "U$26") (pin "1") (pinfunction "G_1") (pintype "bidirectional"))
    )
    (net (code "52") (name "Net-(U$26-S)") (class "Default")
      (node (ref "R51") (pin "1") (pinfunction "1_1") (pintype "passive"))
      (node (ref "U$26") (pin "2") (pinfunction "S_2") (pintype "bidirectional"))
      (node (ref "U$27") (pin "P$1") (pinfunction "P$1_P$1") (pintype "bidirectional"))
    )
    (net (code "53") (name "Net-(U$32-BYP)") (class "Default")
      (node (ref "C40") (pin "1") (pinfunction "1_1") (pintype "passive"))
      (node (ref "U$32") (pin "P$4") (pinfunction "BYP_P$4") (pintype "bidirectional"))
    )
    (net (code "54") (name "P2_1") (class "Default")
      (node (ref "U$20") (pin "10") (pinfunction "P2_1_10") (pintype "bidirectional"))
      (node (ref "U$22") (pin "4") (pinfunction "4A_4") (pintype "bidirectional"))
    )
    (net (code "55") (name "P2_2") (class "Default")
      (node (ref "U$20") (pin "9") (pinfunction "P2_2_9") (pintype "bidirectional"))
      (node (ref "U$22") (pin "3") (pinfunction "3A_3") (pintype "bidirectional"))
    )
    (net (code "56") (name "PACK+") (class "Default")
      (node (ref "C27") (pin "2") (pinfunction "2_2") (pintype "passive"))
      (node (ref "U$28") (pin "P$1") (pinfunction "P$1_P$1") (pintype "bidirectional"))
      (node (ref "U$29") (pin "2") (pinfunction "P$2_2") (pintype "bidirectional"))
      (node (ref "U$31") (pin "P$2") (pinfunction "2_P$2") (pintype "bidirectional"))
    )
    (net (code "57") (name "PACK-") (class "Default")
      (node (ref "C18") (pin "1") (pinfunction "1_1") (pintype "passive"))
      (node (ref "C26") (pin "1") (pinfunction "1_1") (pintype "passive"))
      (node (ref "U$28") (pin "P$2") (pinfunction "P$2_P$2") (pintype "bidirectional"))
      (node (ref "U$29") (pin "1") (pinfunction "P$1_1") (pintype "bidirectional"))
      (node (ref "U$30") (pin "P$1") (pinfunction "P$1_P$1") (pintype "bidirectional"))
      (node (ref "U$4") (pin "3") (pinfunction "D_3") (pintype "bidirectional"))
    )
    (net (code "58") (name "PULSE_EN") (class "Default")
      (node (ref "R22") (pin "2") (pinfunction "2_2") (pintype "passive"))
      (node (ref "U$20") (pin "24") (pinfunction "P1_0_24") (pintype "bidirectional"))
      (node (ref "U$8") (pin "1") (pinfunction "G_1") (pintype "bidirectional"))
    )
    (net (code "59") (name "REGSRC") (class "Default")
      (node (ref "C25") (pin "2") (pinfunction "2_2") (pintype "passive"))
      (node (ref "R51") (pin "2") (pinfunction "2_2") (pintype "passive"))
      (node (ref "U$1") (pin "9") (pinfunction "REGSRC_9") (pintype "bidirectional"))
      (node (ref "U$27") (pin "P$2") (pinfunction "P$2_P$2") (pintype "bidirectional"))
    )
    (net (code "60") (name "SCL") (class "Default")
      (node (ref "JP5") (pin "2") (pinfunction "2_2") (pintype "passive"))
      (node (ref "R57") (pin "1") (pinfunction "1_1") (pintype "passive"))
      (node (ref "U$1") (pin "5") (pinfunction "SCL_5") (pintype "bidirectional"))
      (node (ref "U$20") (pin "14") (pinfunction "SCL_14") (pintype "bidirectional"))
      (node (ref "U$32") (pin "P$2") (pinfunction "SCL_P$2") (pintype "bidirectional"))
    )
    (net (code "61") (name "SDA") (class "Default")
      (node (ref "JP5") (pin "3") (pinfunction "3_3") (pintype "passive"))
      (node (ref "R58") (pin "1") (pinfunction "1_1") (pintype "passive"))
      (node (ref "U$1") (pin "4") (pinfunction "SDA_4") (pintype "bidirectional"))
      (node (ref "U$20") (pin "15") (pinfunction "SDA_15") (pintype "bidirectional"))
      (node (ref "U$32") (pin "P$10") (pinfunction "SDA_P$10") (pintype "bidirectional"))
    )
    (net (code "62") (name "VC5X") (class "Default")
      (node (ref "C1") (pin "1") (pinfunction "1_1") (pintype "passive"))
      (node (ref "C13") (pin "2") (pinfunction "2_2") (pintype "passive"))
      (node (ref "C19") (pin "1") (pinfunction "1_1") (pintype "passive"))
      (node (ref "C21") (pin "2") (pinfunction "2_2") (pintype "passive"))
      (node (ref "C8") (pin "1") (pinfunction "1_1") (pintype "passive"))
      (node (ref "R16") (pin "1") (pinfunction "1_1") (pintype "passive"))
      (node (ref "R20") (pin "2") (pinfunction "2_2") (pintype "passive"))
      (node (ref "R24") (pin "1") (pinfunction "1_1") (pintype "passive"))
      (node (ref "U$1") (pin "10") (pinfunction "VC5X_10") (pintype "bidirectional"))
      (node (ref "U$2") (pin "P$2") (pinfunction "P$2_P$2") (pintype "bidirectional"))
    )
    (net (code "63") (name "VC10X") (class "Default")
      (node (ref "C1") (pin "2") (pinfunction "2_2") (pintype "passive"))
      (node (ref "R30") (pin "1") (pinfunction "1_1") (pintype "passive"))
      (node (ref "U$1") (pin "15") (pinfunction "BAT_15") (pintype "bidirectional"))
      (node (ref "U$9") (pin "P$2") (pinfunction "P$2_P$2") (pintype "bidirectional"))
    )
    (net (code "64") (name "unconnected-(U$20-NC-Pad16)") (class "Default")
      (node (ref "U$20") (pin "16") (pinfunction "NC_16") (pintype "bidirectional"))
    )
    (net (code "65") (name "unconnected-(U$20-NC2-Pad35)") (class "Default")
      (node (ref "U$20") (pin "35") (pinfunction "NC2_35") (pintype "bidirectional"))
    )
    (net (code "66") (name "unconnected-(U$20-P0_1-Pad32)") (class "Default")
      (node (ref "U$20") (pin "32") (pinfunction "P0_1_32") (pintype "bidirectional"))
    )
    (net (code "67") (name "unconnected-(U$20-P0_2-Pad31)") (class "Default")
      (node (ref "U$20") (pin "31") (pinfunction "P0_2_31") (pintype "bidirectional"))
    )
    (net (code "68") (name "unconnected-(U$20-P0_3-Pad30)") (class "Default")
      (node (ref "U$20") (pin "30") (pinfunction "P0_3_30") (pintype "bidirectional"))
    )
    (net (code "69") (name "unconnected-(U$20-P0_4-Pad29)") (class "Default")
      (node (ref "U$20") (pin "29") (pinfunction "P0_4_29") (pintype "bidirectional"))
    )
    (net (code "70") (name "unconnected-(U$20-P1_1-Pad23)") (class "Default")
      (node (ref "U$20") (pin "23") (pinfunction "P1_1_23") (pintype "bidirectional"))
    )
    (net (code "71") (name "unconnected-(U$20-P1_2-Pad22)") (class "Default")
      (node (ref "U$20") (pin "22") (pinfunction "P1_2_22") (pintype "bidirectional"))
    )
    (net (code "72") (name "unconnected-(U$20-P1_3-Pad21)") (class "Default")
      (node (ref "U$20") (pin "21") (pinfunction "P1_3_21") (pintype "bidirectional"))
    )
    (net (code "73") (name "unconnected-(U$20-P1_4-Pad20)") (class "Default")
      (node (ref "U$20") (pin "20") (pinfunction "P1_4_20") (pintype "bidirectional"))
    )
    (net (code "74") (name "unconnected-(U$20-P1_6-Pad13)") (class "Default")
      (node (ref "U$20") (pin "13") (pinfunction "P1_6_13") (pintype "bidirectional"))
    )
    (net (code "75") (name "unconnected-(U$20-P1_7-Pad12)") (class "Default")
      (node (ref "U$20") (pin "12") (pinfunction "P1_7_12") (pintype "bidirectional"))
    )
    (net (code "76") (name "unconnected-(U$20-P2_0-Pad11)") (class "Default")
      (node (ref "U$20") (pin "11") (pinfunction "P2_0_11") (pintype "bidirectional"))
    )
    (net (code "77") (name "unconnected-(U$22-5A-Pad5)") (class "Default")
      (node (ref "U$22") (pin "5") (pinfunction "5A_5") (pintype "bidirectional"))
    )
    (net (code "78") (name "unconnected-(U$22-6A-Pad6)") (class "Default")
      (node (ref "U$22") (pin "6") (pinfunction "6A_6") (pintype "bidirectional"))
    )
    (net (code "79") (name "unconnected-(U$22-8A-Pad8)") (class "Default")
      (node (ref "U$22") (pin "8") (pinfunction "8A_8") (pintype "bidirectional"))
    )
    (net (code "80") (name "unconnected-(U$22-9A-Pad9)") (class "Default")
      (node (ref "U$22") (pin "9") (pinfunction "9A_9") (pintype "bidirectional"))
    )
    (net (code "81") (name "unconnected-(U$22-10A-Pad10)") (class "Default")
      (node (ref "U$22") (pin "10") (pinfunction "10A_10") (pintype "bidirectional"))
    )
    (net (code "82") (name "unconnected-(U$24-Pad6)") (class "Default")
      (node (ref "U$24") (pin "6") (pinfunction "6_6") (pintype "bidirectional"))
    )
    (net (code "83") (name "unconnected-(U$24-PadA1)") (class "Default")
      (node (ref "U$24") (pin "A1") (pinfunction "A1_A1") (pintype "bidirectional"))
    )
    (net (code "84") (name "unconnected-(U$24-PadA2)") (class "Default")
      (node (ref "U$24") (pin "A2") (pinfunction "A2_A2") (pintype "bidirectional"))
    )
    (net (code "85") (name "unconnected-(U$32-INT1-PadP$3)") (class "Default")
      (node (ref "U$32") (pin "P$3") (pinfunction "INT1_P$3") (pintype "bidirectional"))
    )
    (net (code "86") (name "unconnected-(U$32-INT2-PadP$5)") (class "Default")
      (node (ref "U$32") (pin "P$5") (pinfunction "INT2_P$5") (pintype "bidirectional"))
    )
    (net (code "87") (name "unconnected-(U$33-PadA1)") (class "Default")
      (node (ref "U$33") (pin "A1") (pinfunction "A1_A1") (pintype "bidirectional"))
    )
    (net (code "88") (name "unconnected-(U$33-PadA2)") (class "Default")
      (node (ref "U$33") (pin "A2") (pinfunction "A2_A2") (pintype "bidirectional"))
    )
  )
)
